# ESP_SENSOR_STATION_REV1.net
KiCad netlist of a schematic drawn in Altium Designer
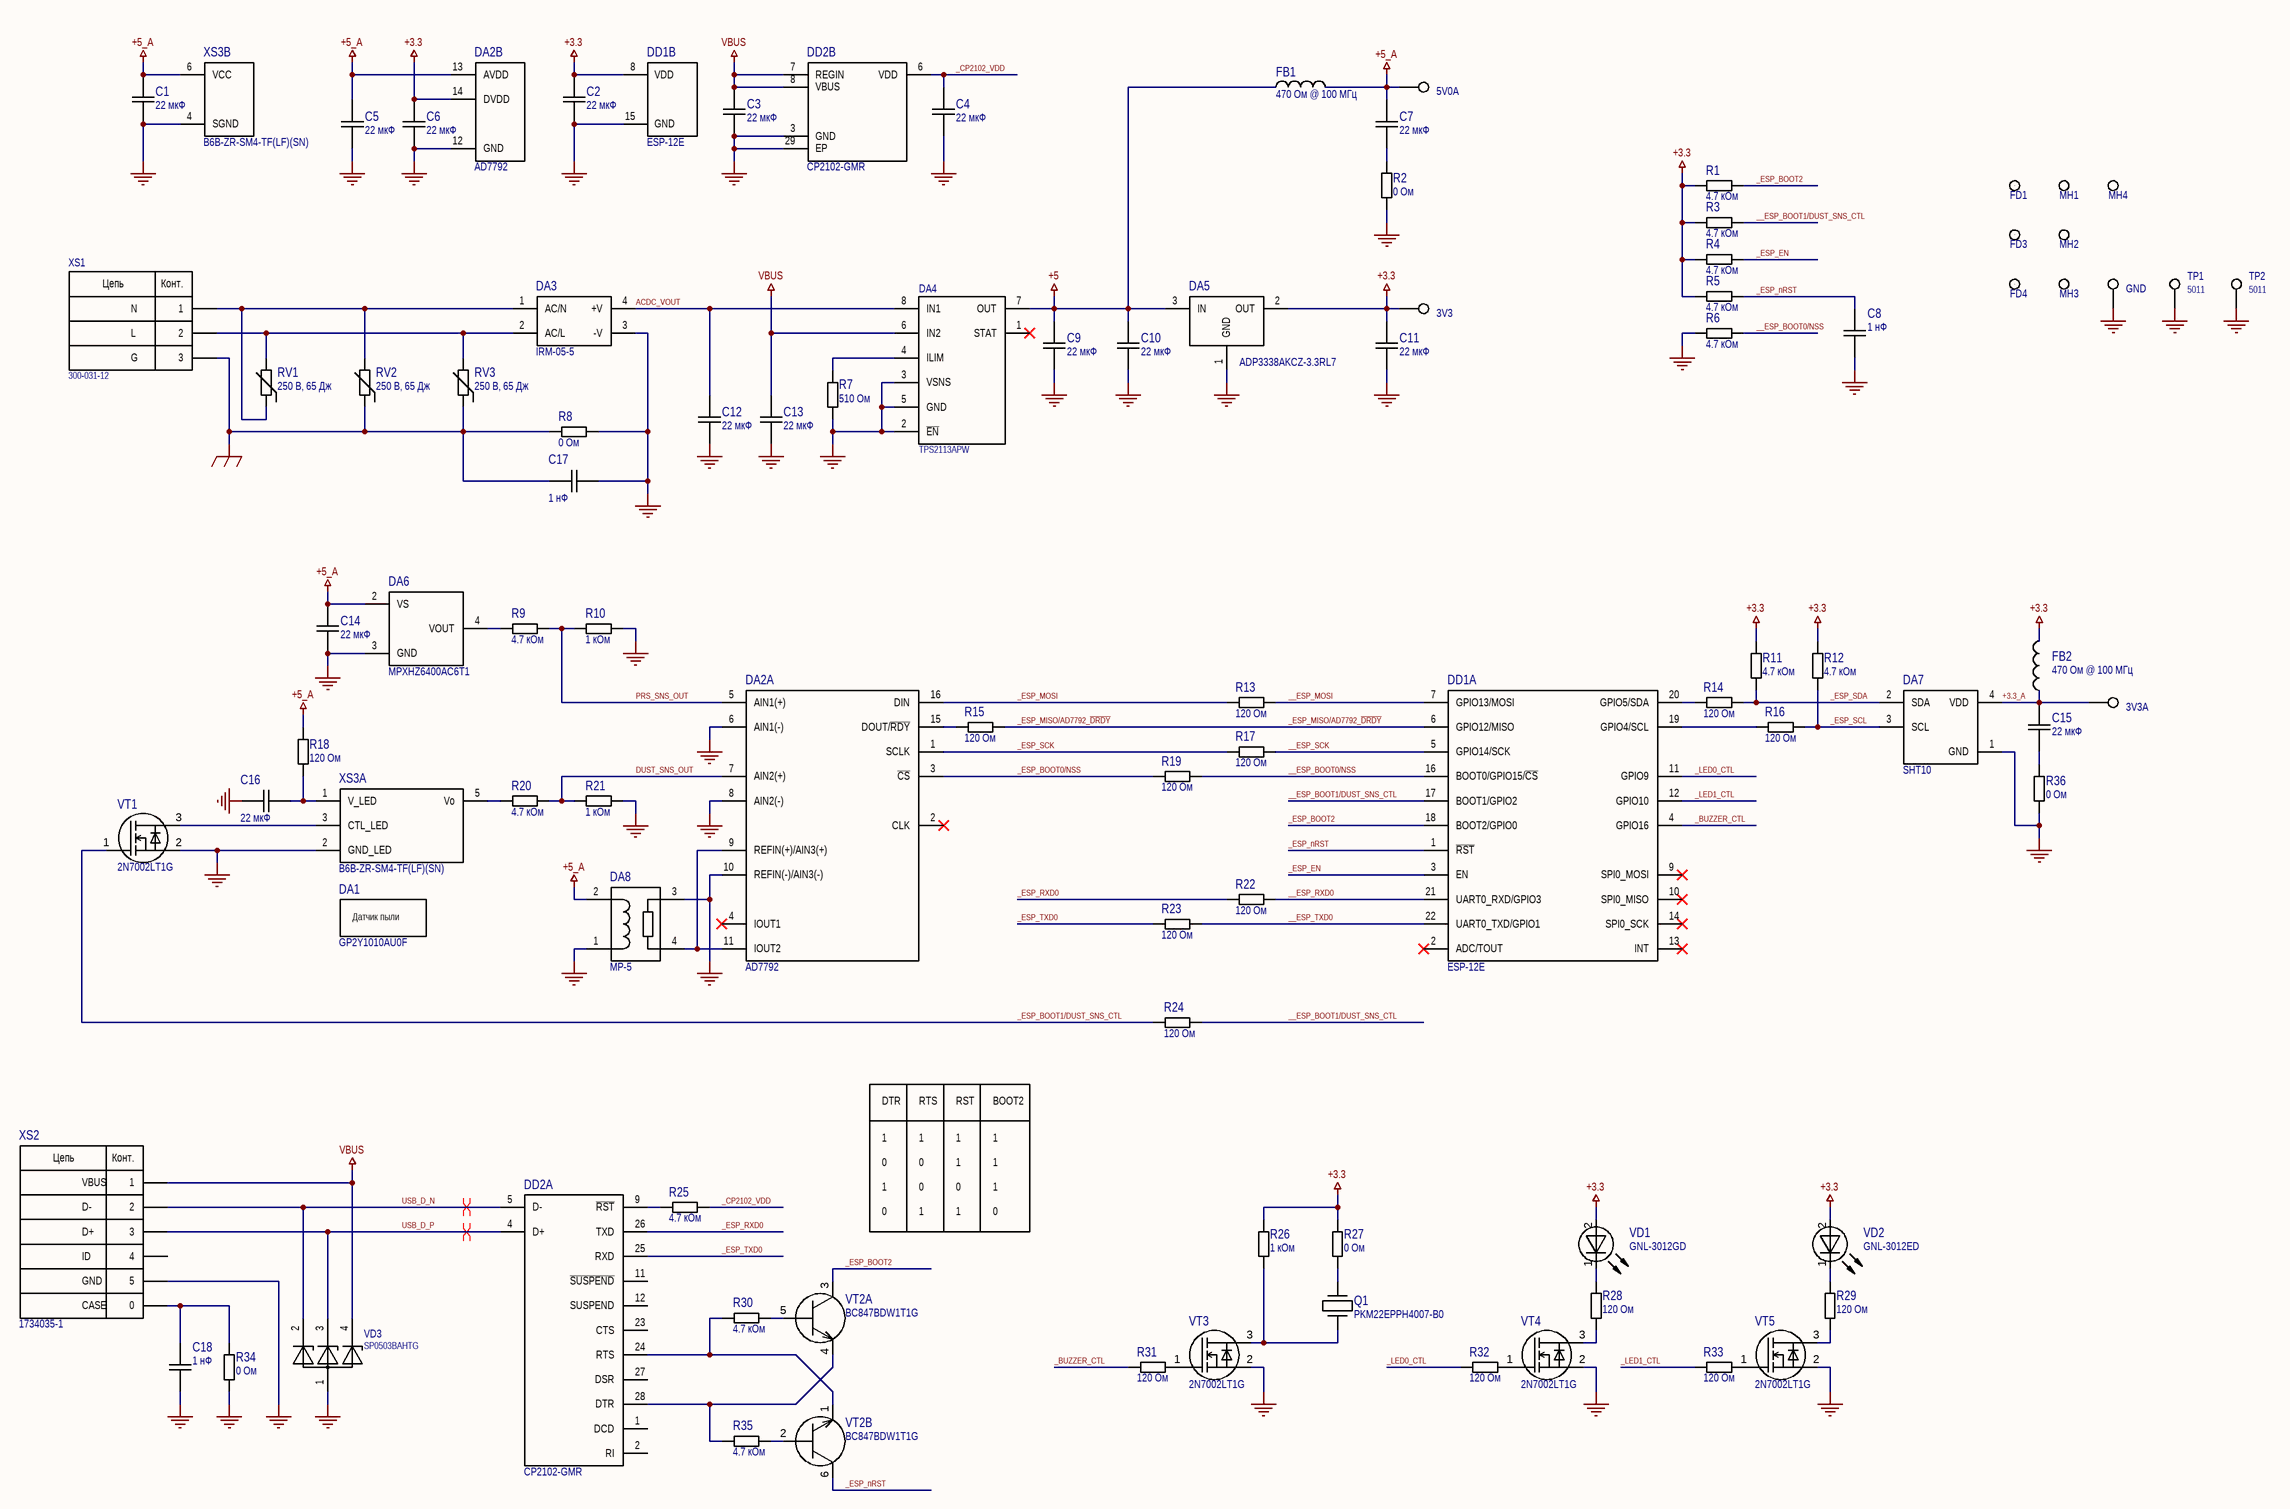
[diagram p0: ESP_SENSOR_STATION_REV1.SchDoc]

(export (version "E")
  (design (tool "Eeschema 10.0.6"))
  (components
    (comp (ref "3V3")
      (value "_TESTPOINT")
      (footprint "_TESTPOINT")
      (libsource (lib "ESP_SENSOR_STATION_REV1") (part "_TESTPOINT"))
    )
    (comp (ref "3V3A")
      (value "_TESTPOINT")
      (footprint "_TESTPOINT")
      (libsource (lib "ESP_SENSOR_STATION_REV1") (part "_TESTPOINT"))
    )
    (comp (ref "5V0A")
      (value "_TESTPOINT")
      (footprint "_TESTPOINT")
      (libsource (lib "ESP_SENSOR_STATION_REV1") (part "_TESTPOINT"))
    )
    (comp (ref "C1")
      (value "22 мкФ")
      (footprint "CAPC1608X08N")
      (libsource (lib "ESP_SENSOR_STATION_REV1") (part "GRM188R61A226ME15D"))
    )
    (comp (ref "C2")
      (value "22 мкФ")
      (footprint "CAPC1608X08N")
      (libsource (lib "ESP_SENSOR_STATION_REV1") (part "GRM188R61A226ME15D"))
    )
    (comp (ref "C3")
      (value "22 мкФ")
      (footprint "CAPC1608X08N")
      (libsource (lib "ESP_SENSOR_STATION_REV1") (part "GRM188R61A226ME15D"))
    )
    (comp (ref "C4")
      (value "22 мкФ")
      (footprint "CAPC1608X08N")
      (libsource (lib "ESP_SENSOR_STATION_REV1") (part "GRM188R61A226ME15D"))
    )
    (comp (ref "C5")
      (value "22 мкФ")
      (footprint "CAPC1608X08N")
      (libsource (lib "ESP_SENSOR_STATION_REV1") (part "GRM188R61A226ME15D"))
    )
    (comp (ref "C6")
      (value "22 мкФ")
      (footprint "CAPC1608X08N")
      (libsource (lib "ESP_SENSOR_STATION_REV1") (part "GRM188R61A226ME15D"))
    )
    (comp (ref "C7")
      (value "22 мкФ")
      (footprint "CAPC1608X08N")
      (libsource (lib "ESP_SENSOR_STATION_REV1") (part "GRM188R61A226ME15D"))
    )
    (comp (ref "C8")
      (value "1 нФ")
      (footprint "CAPC1608X08N")
      (libsource (lib "ESP_SENSOR_STATION_REV1") (part "GRM1885C2A102JA01D"))
    )
    (comp (ref "C9")
      (value "22 мкФ")
      (footprint "CAPC1608X08N")
      (libsource (lib "ESP_SENSOR_STATION_REV1") (part "GRM188R61A226ME15D"))
    )
    (comp (ref "C10")
      (value "22 мкФ")
      (footprint "CAPC1608X08N")
      (libsource (lib "ESP_SENSOR_STATION_REV1") (part "GRM188R61A226ME15D"))
    )
    (comp (ref "C11")
      (value "22 мкФ")
      (footprint "CAPC1608X08N")
      (libsource (lib "ESP_SENSOR_STATION_REV1") (part "GRM188R61A226ME15D"))
    )
    (comp (ref "C12")
      (value "22 мкФ")
      (footprint "CAPC1608X08N")
      (libsource (lib "ESP_SENSOR_STATION_REV1") (part "GRM188R61A226ME15D"))
    )
    (comp (ref "C13")
      (value "22 мкФ")
      (footprint "CAPC1608X08N")
      (libsource (lib "ESP_SENSOR_STATION_REV1") (part "GRM188R61A226ME15D"))
    )
    (comp (ref "C14")
      (value "22 мкФ")
      (footprint "CAPC1608X08N")
      (libsource (lib "ESP_SENSOR_STATION_REV1") (part "GRM188R61A226ME15D"))
    )
    (comp (ref "C15")
      (value "22 мкФ")
      (footprint "CAPC1608X08N")
      (libsource (lib "ESP_SENSOR_STATION_REV1") (part "GRM188R61A226ME15D"))
    )
    (comp (ref "C16")
      (value "22 мкФ")
      (footprint "CAPC1608X08N")
      (libsource (lib "ESP_SENSOR_STATION_REV1") (part "GRM188R61A226ME15D"))
    )
    (comp (ref "C17")
      (value "1 нФ")
      (footprint "CAPC1608X08N")
      (libsource (lib "ESP_SENSOR_STATION_REV1") (part "GRM1885C2A102JA01D"))
    )
    (comp (ref "C18")
      (value "1 нФ")
      (footprint "CAPC1608X08N")
      (libsource (lib "ESP_SENSOR_STATION_REV1") (part "GRM1885C2A102JA01D"))
    )
    (comp (ref "DA1")
      (value "GP2Y1010AU0F")
      (footprint "GP2Y1010AU0F")
      (libsource (lib "ESP_SENSOR_STATION_REV1") (part "GP2Y1010AU0F"))
    )
    (comp (ref "DA2")
      (value "AD7792")
      (footprint "TSOP65P640X120-16N")
      (libsource (lib "ESP_SENSOR_STATION_REV1") (part "AD7792"))
    )
    (comp (ref "DA3")
      (value "IRM-05-5")
      (footprint "IRM-05")
      (libsource (lib "ESP_SENSOR_STATION_REV1") (part "IRM-05-5"))
    )
    (comp (ref "DA4")
      (value "TPS2113APW")
      (footprint "TSOP65P640X120-8N")
      (libsource (lib "ESP_SENSOR_STATION_REV1") (part "TPS2113APW"))
    )
    (comp (ref "DA5")
      (value "ADP3338AKCZ-3.3RL7")
      (footprint "SOT230P700X180-4N")
      (libsource (lib "ESP_SENSOR_STATION_REV1") (part "ADP3338AKCZ-3.3RL7"))
    )
    (comp (ref "DA6")
      (value "MPXHZ6400AC6T1")
      (footprint "MPXHZ6400AC6T1")
      (libsource (lib "ESP_SENSOR_STATION_REV1") (part "MPXHZ6400AC6T1"))
    )
    (comp (ref "DA7")
      (value "SHT10")
      (footprint "SHT1x")
      (libsource (lib "ESP_SENSOR_STATION_REV1") (part "SHT10"))
    )
    (comp (ref "DA8")
      (value "MP-5")
      (footprint "MP-5")
      (libsource (lib "ESP_SENSOR_STATION_REV1") (part "MP-5"))
    )
    (comp (ref "DD1")
      (value "ESP-12E")
      (footprint "ESP-12E")
      (libsource (lib "ESP_SENSOR_STATION_REV1") (part "ESP-12E"))
    )
    (comp (ref "DD2")
      (value "CP2102-GMR")
      (footprint "QFN50P500X500X100_HS-29N")
      (libsource (lib "ESP_SENSOR_STATION_REV1") (part "CP2102-GMR"))
    )
    (comp (ref "FB1")
      (value "470 Ом @ 100 МГц")
      (footprint "INDC1608X08N")
      (libsource (lib "ESP_SENSOR_STATION_REV1") (part "BLM18PG471SN1D"))
    )
    (comp (ref "FB2")
      (value "470 Ом @ 100 МГц")
      (footprint "INDC1608X08N")
      (libsource (lib "ESP_SENSOR_STATION_REV1") (part "BLM18PG471SN1D"))
    )
    (comp (ref "FD1")
      (value "_FIDUCIAL")
      (footprint "_FIDUCIAL")
      (libsource (lib "ESP_SENSOR_STATION_REV1") (part "_FIDUCIAL"))
    )
    (comp (ref "FD3")
      (value "_FIDUCIAL")
      (footprint "_FIDUCIAL")
      (libsource (lib "ESP_SENSOR_STATION_REV1") (part "_FIDUCIAL"))
    )
    (comp (ref "FD4")
      (value "_FIDUCIAL")
      (footprint "_FIDUCIAL")
      (libsource (lib "ESP_SENSOR_STATION_REV1") (part "_FIDUCIAL"))
    )
    (comp (ref "GND")
      (value "_TESTPOINT")
      (footprint "_TESTPOINT")
      (libsource (lib "ESP_SENSOR_STATION_REV1") (part "_TESTPOINT"))
    )
    (comp (ref "MH1")
      (value "_MOUNTING_HOLE_M3")
      (footprint "_MOUNTING_HOLE_M3")
      (libsource (lib "ESP_SENSOR_STATION_REV1") (part "_MOUNTING_HOLE_M3"))
    )
    (comp (ref "MH2")
      (value "_MOUNTING_HOLE_M3")
      (footprint "_MOUNTING_HOLE_M3")
      (libsource (lib "ESP_SENSOR_STATION_REV1") (part "_MOUNTING_HOLE_M3"))
    )
    (comp (ref "MH3")
      (value "_MOUNTING_HOLE_M3")
      (footprint "_MOUNTING_HOLE_M3")
      (libsource (lib "ESP_SENSOR_STATION_REV1") (part "_MOUNTING_HOLE_M3"))
    )
    (comp (ref "MH4")
      (value "_MOUNTING_HOLE_M3")
      (footprint "_MOUNTING_HOLE_M3")
      (libsource (lib "ESP_SENSOR_STATION_REV1") (part "_MOUNTING_HOLE_M3"))
    )
    (comp (ref "Q1")
      (value "PKM22EPPH4007-B0")
      (footprint "PKM22EPPH4007-B0")
      (libsource (lib "ESP_SENSOR_STATION_REV1") (part "PKM22EPPH4007-B0"))
    )
    (comp (ref "R1")
      (value "4.7 кОм")
      (footprint "RESC1608X06N")
      (libsource (lib "ESP_SENSOR_STATION_REV1") (part "RC0603FR-074K7L"))
    )
    (comp (ref "R2")
      (value "0 Ом")
      (footprint "RESC1608X06N")
      (libsource (lib "ESP_SENSOR_STATION_REV1") (part "RC0603FR-070RL"))
    )
    (comp (ref "R3")
      (value "4.7 кОм")
      (footprint "RESC1608X06N")
      (libsource (lib "ESP_SENSOR_STATION_REV1") (part "RC0603FR-074K7L"))
    )
    (comp (ref "R4")
      (value "4.7 кОм")
      (footprint "RESC1608X06N")
      (libsource (lib "ESP_SENSOR_STATION_REV1") (part "RC0603FR-074K7L"))
    )
    (comp (ref "R5")
      (value "4.7 кОм")
      (footprint "RESC1608X06N")
      (libsource (lib "ESP_SENSOR_STATION_REV1") (part "RC0603FR-074K7L"))
    )
    (comp (ref "R6")
      (value "4.7 кОм")
      (footprint "RESC1608X06N")
      (libsource (lib "ESP_SENSOR_STATION_REV1") (part "RC0603FR-074K7L"))
    )
    (comp (ref "R7")
      (value "510 Ом")
      (footprint "RESC1608X06N")
      (libsource (lib "ESP_SENSOR_STATION_REV1") (part "RC0603FR-07510RL"))
    )
    (comp (ref "R8")
      (value "0 Ом")
      (footprint "RESC1608X06N")
      (libsource (lib "ESP_SENSOR_STATION_REV1") (part "RC0603FR-070RL"))
    )
    (comp (ref "R9")
      (value "4.7 кОм")
      (footprint "RESC1608X06N")
      (libsource (lib "ESP_SENSOR_STATION_REV1") (part "RC0603FR-074K7L"))
    )
    (comp (ref "R10")
      (value "1 кОм")
      (footprint "RESC1608X06N")
      (libsource (lib "ESP_SENSOR_STATION_REV1") (part "RC0603FR-071KL"))
    )
    (comp (ref "R11")
      (value "4.7 кОм")
      (footprint "RESC1608X06N")
      (libsource (lib "ESP_SENSOR_STATION_REV1") (part "RC0603FR-074K7L"))
    )
    (comp (ref "R12")
      (value "4.7 кОм")
      (footprint "RESC1608X06N")
      (libsource (lib "ESP_SENSOR_STATION_REV1") (part "RC0603FR-074K7L"))
    )
    (comp (ref "R13")
      (value "120 Ом")
      (footprint "RESC1608X06N")
      (libsource (lib "ESP_SENSOR_STATION_REV1") (part "RC0603FR-07120RL"))
    )
    (comp (ref "R14")
      (value "120 Ом")
      (footprint "RESC1608X06N")
      (libsource (lib "ESP_SENSOR_STATION_REV1") (part "RC0603FR-07120RL"))
    )
    (comp (ref "R15")
      (value "120 Ом")
      (footprint "RESC1608X06N")
      (libsource (lib "ESP_SENSOR_STATION_REV1") (part "RC0603FR-07120RL"))
    )
    (comp (ref "R16")
      (value "120 Ом")
      (footprint "RESC1608X06N")
      (libsource (lib "ESP_SENSOR_STATION_REV1") (part "RC0603FR-07120RL"))
    )
    (comp (ref "R17")
      (value "120 Ом")
      (footprint "RESC1608X06N")
      (libsource (lib "ESP_SENSOR_STATION_REV1") (part "RC0603FR-07120RL"))
    )
    (comp (ref "R18")
      (value "120 Ом")
      (footprint "RESC1608X06N")
      (libsource (lib "ESP_SENSOR_STATION_REV1") (part "RC0603FR-07120RL"))
    )
    (comp (ref "R19")
      (value "120 Ом")
      (footprint "RESC1608X06N")
      (libsource (lib "ESP_SENSOR_STATION_REV1") (part "RC0603FR-07120RL"))
    )
    (comp (ref "R20")
      (value "4.7 кОм")
      (footprint "RESC1608X06N")
      (libsource (lib "ESP_SENSOR_STATION_REV1") (part "RC0603FR-074K7L"))
    )
    (comp (ref "R21")
      (value "1 кОм")
      (footprint "RESC1608X06N")
      (libsource (lib "ESP_SENSOR_STATION_REV1") (part "RC0603FR-071KL"))
    )
    (comp (ref "R22")
      (value "120 Ом")
      (footprint "RESC1608X06N")
      (libsource (lib "ESP_SENSOR_STATION_REV1") (part "RC0603FR-07120RL"))
    )
    (comp (ref "R23")
      (value "120 Ом")
      (footprint "RESC1608X06N")
      (libsource (lib "ESP_SENSOR_STATION_REV1") (part "RC0603FR-07120RL"))
    )
    (comp (ref "R24")
      (value "120 Ом")
      (footprint "RESC1608X06N")
      (libsource (lib "ESP_SENSOR_STATION_REV1") (part "RC0603FR-07120RL"))
    )
    (comp (ref "R25")
      (value "4.7 кОм")
      (footprint "RESC1608X06N")
      (libsource (lib "ESP_SENSOR_STATION_REV1") (part "RC0603FR-074K7L"))
    )
    (comp (ref "R26")
      (value "1 кОм")
      (footprint "RESC1608X06N")
      (libsource (lib "ESP_SENSOR_STATION_REV1") (part "RC0603FR-071KL"))
    )
    (comp (ref "R27")
      (value "0 Ом")
      (footprint "RESC1608X06N")
      (libsource (lib "ESP_SENSOR_STATION_REV1") (part "RC0603FR-070RL"))
    )
    (comp (ref "R28")
      (value "120 Ом")
      (footprint "RESC1608X06N")
      (libsource (lib "ESP_SENSOR_STATION_REV1") (part "RC0603FR-07120RL"))
    )
    (comp (ref "R29")
      (value "120 Ом")
      (footprint "RESC1608X06N")
      (libsource (lib "ESP_SENSOR_STATION_REV1") (part "RC0603FR-07120RL"))
    )
    (comp (ref "R30")
      (value "4.7 кОм")
      (footprint "RESC1608X06N")
      (libsource (lib "ESP_SENSOR_STATION_REV1") (part "RC0603FR-074K7L"))
    )
    (comp (ref "R31")
      (value "120 Ом")
      (footprint "RESC1608X06N")
      (libsource (lib "ESP_SENSOR_STATION_REV1") (part "RC0603FR-07120RL"))
    )
    (comp (ref "R32")
      (value "120 Ом")
      (footprint "RESC1608X06N")
      (libsource (lib "ESP_SENSOR_STATION_REV1") (part "RC0603FR-07120RL"))
    )
    (comp (ref "R33")
      (value "120 Ом")
      (footprint "RESC1608X06N")
      (libsource (lib "ESP_SENSOR_STATION_REV1") (part "RC0603FR-07120RL"))
    )
    (comp (ref "R34")
      (value "0 Ом")
      (footprint "RESC1608X06N")
      (libsource (lib "ESP_SENSOR_STATION_REV1") (part "RC0603FR-070RL"))
    )
    (comp (ref "R35")
      (value "4.7 кОм")
      (footprint "RESC1608X06N")
      (libsource (lib "ESP_SENSOR_STATION_REV1") (part "RC0603FR-074K7L"))
    )
    (comp (ref "R36")
      (value "0 Ом")
      (footprint "RESC1608X06N")
      (libsource (lib "ESP_SENSOR_STATION_REV1") (part "RC0603FR-070RL"))
    )
    (comp (ref "RV1")
      (value "250 В, 65 Дж")
      (footprint "B72214S0251K101")
      (libsource (lib "ESP_SENSOR_STATION_REV1") (part "B72214S0251K101"))
    )
    (comp (ref "RV2")
      (value "250 В, 65 Дж")
      (footprint "B72214S0251K101")
      (libsource (lib "ESP_SENSOR_STATION_REV1") (part "B72214S0251K101"))
    )
    (comp (ref "RV3")
      (value "250 В, 65 Дж")
      (footprint "B72214S0251K101")
      (libsource (lib "ESP_SENSOR_STATION_REV1") (part "B72214S0251K101"))
    )
    (comp (ref "TP1")
      (value "5011")
      (footprint "5011")
      (libsource (lib "ESP_SENSOR_STATION_REV1") (part "5011"))
    )
    (comp (ref "TP2")
      (value "5011")
      (footprint "5011")
      (libsource (lib "ESP_SENSOR_STATION_REV1") (part "5011"))
    )
    (comp (ref "VD1")
      (value "GNL-3012GD")
      (footprint "GNL-3012GD")
      (libsource (lib "ESP_SENSOR_STATION_REV1") (part "GNL-3012GD"))
    )
    (comp (ref "VD2")
      (value "GNL-3012ED")
      (footprint "GNL-3012ED")
      (libsource (lib "ESP_SENSOR_STATION_REV1") (part "GNL-3012ED"))
    )
    (comp (ref "VD3")
      (value "SP0503BAHTG")
      (footprint "SOT190P237X122-4N")
      (libsource (lib "ESP_SENSOR_STATION_REV1") (part "SP0503BAHTG"))
    )
    (comp (ref "VT1")
      (value "2N7002LT1G")
      (footprint "SOT95P237X111-3N")
      (libsource (lib "ESP_SENSOR_STATION_REV1") (part "2N7002LT1G"))
    )
    (comp (ref "VT2")
      (value "BC847BDW1T1G")
      (footprint "SOT65P210X110-6N")
      (libsource (lib "ESP_SENSOR_STATION_REV1") (part "BC847BDW1T1G"))
    )
    (comp (ref "VT3")
      (value "2N7002LT1G")
      (footprint "SOT95P237X111-3N")
      (libsource (lib "ESP_SENSOR_STATION_REV1") (part "2N7002LT1G"))
    )
    (comp (ref "VT4")
      (value "2N7002LT1G")
      (footprint "SOT95P237X111-3N")
      (libsource (lib "ESP_SENSOR_STATION_REV1") (part "2N7002LT1G"))
    )
    (comp (ref "VT5")
      (value "2N7002LT1G")
      (footprint "SOT95P237X111-3N")
      (libsource (lib "ESP_SENSOR_STATION_REV1") (part "2N7002LT1G"))
    )
    (comp (ref "XS1")
      (value "300-031-12")
      (footprint "300-031-12")
      (libsource (lib "ESP_SENSOR_STATION_REV1") (part "300-031-12"))
    )
    (comp (ref "XS2")
      (value "1734035-1")
      (footprint "1734035-1")
      (libsource (lib "ESP_SENSOR_STATION_REV1") (part "1734035-1"))
    )
    (comp (ref "XS3")
      (value "B6B-ZR-SM4-TF(LF)(SN)")
      (footprint "B6B-ZR-SM4-TF(LF)(SN)")
      (libsource (lib "ESP_SENSOR_STATION_REV1") (part "B6B-ZR-SM4-TF(LF)(SN)"))
    )
  )
  (nets
    (net (code "1") (name "+3.3") (class "Default")
      (node (ref "3V3") (pin "1") (pinfunction "1_1") (pintype "passive"))
      (node (ref "C11") (pin "2") (pinfunction "2_2") (pintype "passive"))
      (node (ref "C2") (pin "2") (pinfunction "2_2") (pintype "passive"))
      (node (ref "C6") (pin "2") (pinfunction "2_2") (pintype "passive"))
      (node (ref "DA2") (pin "14") (pinfunction "DVDD_14") (pintype "passive"))
      (node (ref "DA5") (pin "2") (pinfunction "OUT_2") (pintype "passive"))
      (node (ref "DD1") (pin "8") (pinfunction "VDD_8") (pintype "passive"))
      (node (ref "FB2") (pin "2") (pinfunction "2_2") (pintype "passive"))
      (node (ref "R1") (pin "1") (pinfunction "1_1") (pintype "passive"))
      (node (ref "R11") (pin "1") (pinfunction "1_1") (pintype "passive"))
      (node (ref "R12") (pin "1") (pinfunction "1_1") (pintype "passive"))
      (node (ref "R26") (pin "2") (pinfunction "2_2") (pintype "passive"))
      (node (ref "R27") (pin "2") (pinfunction "2_2") (pintype "passive"))
      (node (ref "R3") (pin "1") (pinfunction "1_1") (pintype "passive"))
      (node (ref "R4") (pin "1") (pinfunction "1_1") (pintype "passive"))
      (node (ref "R5") (pin "1") (pinfunction "1_1") (pintype "passive"))
      (node (ref "VD1") (pin "2") (pinfunction "A_2") (pintype "passive"))
      (node (ref "VD2") (pin "2") (pinfunction "A_2") (pintype "passive"))
    )
    (net (code "2") (name "+5") (class "Default")
      (node (ref "C10") (pin "2") (pinfunction "2_2") (pintype "passive"))
      (node (ref "C9") (pin "2") (pinfunction "2_2") (pintype "passive"))
      (node (ref "DA4") (pin "7") (pinfunction "OUT_7") (pintype "passive"))
      (node (ref "DA5") (pin "3") (pinfunction "IN_3") (pintype "passive"))
      (node (ref "FB1") (pin "1") (pinfunction "1_1") (pintype "passive"))
    )
    (net (code "3") (name "+5_A") (class "Default")
      (node (ref "5V0A") (pin "1") (pinfunction "1_1") (pintype "passive"))
      (node (ref "C1") (pin "2") (pinfunction "2_2") (pintype "passive"))
      (node (ref "C14") (pin "2") (pinfunction "2_2") (pintype "passive"))
      (node (ref "C5") (pin "2") (pinfunction "2_2") (pintype "passive"))
      (node (ref "C7") (pin "2") (pinfunction "2_2") (pintype "passive"))
      (node (ref "DA2") (pin "13") (pinfunction "AVDD_13") (pintype "passive"))
      (node (ref "DA6") (pin "2") (pinfunction "VS_2") (pintype "passive"))
      (node (ref "DA8") (pin "2") (pinfunction "2_2") (pintype "passive"))
      (node (ref "FB1") (pin "2") (pinfunction "2_2") (pintype "passive"))
      (node (ref "R18") (pin "1") (pinfunction "1_1") (pintype "passive"))
      (node (ref "XS3") (pin "6") (pinfunction "VCC_6") (pintype "passive"))
    )
    (net (code "4") (name "/+3.3_A") (class "Default")
      (node (ref "3V3A") (pin "1") (pinfunction "1_1") (pintype "passive"))
      (node (ref "C15") (pin "2") (pinfunction "2_2") (pintype "passive"))
      (node (ref "DA7") (pin "4") (pinfunction "VDD_4") (pintype "passive"))
      (node (ref "FB2") (pin "1") (pinfunction "1_1") (pintype "passive"))
    )
    (net (code "5") (name "/ACDC_VOUT") (class "Default")
      (node (ref "C12") (pin "2") (pinfunction "2_2") (pintype "passive"))
      (node (ref "DA3") (pin "4") (pinfunction "+V_4") (pintype "passive"))
      (node (ref "DA4") (pin "8") (pinfunction "IN1_8") (pintype "passive"))
    )
    (net (code "6") (name "/DUST_SNS_OUT") (class "Default")
      (node (ref "DA2") (pin "7") (pinfunction "AIN2(+)_7") (pintype "passive"))
      (node (ref "R20") (pin "2") (pinfunction "2_2") (pintype "passive"))
      (node (ref "R21") (pin "2") (pinfunction "2_2") (pintype "passive"))
    )
    (net (code "7") (name "/PRS_SNS_OUT") (class "Default")
      (node (ref "DA2") (pin "5") (pinfunction "AIN1(+)_5") (pintype "passive"))
      (node (ref "R10") (pin "2") (pinfunction "2_2") (pintype "passive"))
      (node (ref "R9") (pin "2") (pinfunction "2_2") (pintype "passive"))
    )
    (net (code "8") (name "/USB_D_N") (class "Default")
      (node (ref "DD2") (pin "5") (pinfunction "D-_5") (pintype "passive"))
      (node (ref "VD3") (pin "2") (pinfunction "2_2") (pintype "passive"))
      (node (ref "XS2") (pin "2") (pinfunction "2_2") (pintype "passive"))
    )
    (net (code "9") (name "/USB_D_P") (class "Default")
      (node (ref "DD2") (pin "4") (pinfunction "D+_4") (pintype "passive"))
      (node (ref "VD3") (pin "3") (pinfunction "3_3") (pintype "passive"))
      (node (ref "XS2") (pin "3") (pinfunction "3_3") (pintype "passive"))
    )
    (net (code "10") (name "/_BUZZER_CTL") (class "Default")
      (node (ref "DD1") (pin "4") (pinfunction "GPIO16_4") (pintype "passive"))
      (node (ref "R31") (pin "2") (pinfunction "2_2") (pintype "passive"))
    )
    (net (code "11") (name "/_CP2102_VDD") (class "Default")
      (node (ref "C4") (pin "2") (pinfunction "2_2") (pintype "passive"))
      (node (ref "DD2") (pin "6") (pinfunction "VDD_6") (pintype "passive"))
      (node (ref "R25") (pin "1") (pinfunction "1_1") (pintype "passive"))
    )
    (net (code "12") (name "/_ESP_BOOT0{slash}NSS") (class "Default")
      (node (ref "DA2") (pin "3") (pinfunction "~{CS}_3") (pintype "passive"))
      (node (ref "R19") (pin "2") (pinfunction "2_2") (pintype "passive"))
    )
    (net (code "13") (name "/_ESP_BOOT1{slash}DUST_SNS_CTL") (class "Default")
      (node (ref "R24") (pin "2") (pinfunction "2_2") (pintype "passive"))
      (node (ref "VT1") (pin "1") (pinfunction "G_1") (pintype "passive"))
    )
    (net (code "14") (name "/_ESP_BOOT2") (class "Default")
      (node (ref "DD1") (pin "18") (pinfunction "BOOT2/GPIO0_18") (pintype "passive"))
      (node (ref "R1") (pin "2") (pinfunction "2_2") (pintype "passive"))
      (node (ref "VT2") (pin "3") (pinfunction "C1_3") (pintype "passive"))
    )
    (net (code "15") (name "/_ESP_EN") (class "Default")
      (node (ref "DD1") (pin "3") (pinfunction "EN_3") (pintype "passive"))
      (node (ref "R4") (pin "2") (pinfunction "2_2") (pintype "passive"))
    )
    (net (code "16") (name "/_ESP_MISO{slash}AD7792_~{DRDY}") (class "Default")
      (node (ref "DD1") (pin "6") (pinfunction "GPIO12/MISO_6") (pintype "passive"))
      (node (ref "R15") (pin "1") (pinfunction "1_1") (pintype "passive"))
    )
    (net (code "17") (name "/_ESP_MOSI") (class "Default")
      (node (ref "DA2") (pin "16") (pinfunction "DIN_16") (pintype "passive"))
      (node (ref "R13") (pin "2") (pinfunction "2_2") (pintype "passive"))
    )
    (net (code "18") (name "/_ESP_RXD0") (class "Default")
      (node (ref "DD2") (pin "26") (pinfunction "TXD_26") (pintype "passive"))
      (node (ref "R22") (pin "2") (pinfunction "2_2") (pintype "passive"))
    )
    (net (code "19") (name "/_ESP_SCK") (class "Default")
      (node (ref "DA2") (pin "1") (pinfunction "SCLK_1") (pintype "passive"))
      (node (ref "R17") (pin "2") (pinfunction "2_2") (pintype "passive"))
    )
    (net (code "20") (name "/_ESP_SCL") (class "Default")
      (node (ref "DA7") (pin "3") (pinfunction "SCL_3") (pintype "passive"))
      (node (ref "R12") (pin "2") (pinfunction "2_2") (pintype "passive"))
      (node (ref "R16") (pin "1") (pinfunction "1_1") (pintype "passive"))
    )
    (net (code "21") (name "/_ESP_SDA") (class "Default")
      (node (ref "DA7") (pin "2") (pinfunction "SDA_2") (pintype "passive"))
      (node (ref "R11") (pin "2") (pinfunction "2_2") (pintype "passive"))
      (node (ref "R14") (pin "1") (pinfunction "1_1") (pintype "passive"))
    )
    (net (code "22") (name "/_ESP_TXD0") (class "Default")
      (node (ref "DD2") (pin "25") (pinfunction "RXD_25") (pintype "passive"))
      (node (ref "R23") (pin "2") (pinfunction "2_2") (pintype "passive"))
    )
    (net (code "23") (name "/_ESP_nRST") (class "Default")
      (node (ref "C8") (pin "2") (pinfunction "2_2") (pintype "passive"))
      (node (ref "DD1") (pin "1") (pinfunction "~{RST}_1") (pintype "passive"))
      (node (ref "R5") (pin "2") (pinfunction "2_2") (pintype "passive"))
      (node (ref "VT2") (pin "6") (pinfunction "C2_6") (pintype "passive"))
    )
    (net (code "24") (name "/_LED0_CTL") (class "Default")
      (node (ref "DD1") (pin "11") (pinfunction "GPIO9_11") (pintype "passive"))
      (node (ref "R32") (pin "2") (pinfunction "2_2") (pintype "passive"))
    )
    (net (code "25") (name "/_LED1_CTL") (class "Default")
      (node (ref "DD1") (pin "12") (pinfunction "GPIO10_12") (pintype "passive"))
      (node (ref "R33") (pin "2") (pinfunction "2_2") (pintype "passive"))
    )
    (net (code "26") (name "/__ESP_BOOT0{slash}NSS") (class "Default")
      (node (ref "DD1") (pin "16") (pinfunction "BOOT0/GPIO15/~{CS}_16") (pintype "passive"))
      (node (ref "R19") (pin "1") (pinfunction "1_1") (pintype "passive"))
      (node (ref "R6") (pin "2") (pinfunction "2_2") (pintype "passive"))
    )
    (net (code "27") (name "/__ESP_BOOT1{slash}DUST_SNS_CTL") (class "Default")
      (node (ref "DD1") (pin "17") (pinfunction "BOOT1/GPIO2_17") (pintype "passive"))
      (node (ref "R24") (pin "1") (pinfunction "1_1") (pintype "passive"))
      (node (ref "R3") (pin "2") (pinfunction "2_2") (pintype "passive"))
    )
    (net (code "28") (name "/__ESP_MOSI") (class "Default")
      (node (ref "DD1") (pin "7") (pinfunction "GPIO13/MOSI_7") (pintype "passive"))
      (node (ref "R13") (pin "1") (pinfunction "1_1") (pintype "passive"))
    )
    (net (code "29") (name "/__ESP_RXD0") (class "Default")
      (node (ref "DD1") (pin "21") (pinfunction "UART0_RXD/GPIO3_21") (pintype "passive"))
      (node (ref "R22") (pin "1") (pinfunction "1_1") (pintype "passive"))
    )
    (net (code "30") (name "/__ESP_SCK") (class "Default")
      (node (ref "DD1") (pin "5") (pinfunction "GPIO14/SCK_5") (pintype "passive"))
      (node (ref "R17") (pin "1") (pinfunction "1_1") (pintype "passive"))
    )
    (net (code "31") (name "/__ESP_TXD0") (class "Default")
      (node (ref "DD1") (pin "22") (pinfunction "UART0_TXD/GPIO1_22") (pintype "passive"))
      (node (ref "R23") (pin "1") (pinfunction "1_1") (pintype "passive"))
    )
    (net (code "32") (name "GND") (class "Default")
      (node (ref "C1") (pin "1") (pinfunction "1_1") (pintype "passive"))
      (node (ref "C10") (pin "1") (pinfunction "1_1") (pintype "passive"))
      (node (ref "C11") (pin "1") (pinfunction "1_1") (pintype "passive"))
      (node (ref "C12") (pin "1") (pinfunction "1_1") (pintype "passive"))
      (node (ref "C13") (pin "1") (pinfunction "1_1") (pintype "passive"))
      (node (ref "C14") (pin "1") (pinfunction "1_1") (pintype "passive"))
      (node (ref "C16") (pin "1") (pinfunction "1_1") (pintype "passive"))
      (node (ref "C17") (pin "1") (pinfunction "1_1") (pintype "passive"))
      (node (ref "C18") (pin "2") (pinfunction "2_2") (pintype "passive"))
      (node (ref "C2") (pin "1") (pinfunction "1_1") (pintype "passive"))
      (node (ref "C3") (pin "1") (pinfunction "1_1") (pintype "passive"))
      (node (ref "C4") (pin "1") (pinfunction "1_1") (pintype "passive"))
      (node (ref "C5") (pin "1") (pinfunction "1_1") (pintype "passive"))
      (node (ref "C6") (pin "1") (pinfunction "1_1") (pintype "passive"))
      (node (ref "C8") (pin "1") (pinfunction "1_1") (pintype "passive"))
      (node (ref "C9") (pin "1") (pinfunction "1_1") (pintype "passive"))
      (node (ref "DA2") (pin "10") (pinfunction "REFIN(-)/AIN3(-)_10") (pintype "passive"))
      (node (ref "DA2") (pin "12") (pinfunction "GND_12") (pintype "passive"))
      (node (ref "DA2") (pin "6") (pinfunction "AIN1(-)_6") (pintype "passive"))
      (node (ref "DA2") (pin "8") (pinfunction "AIN2(-)_8") (pintype "passive"))
      (node (ref "DA3") (pin "3") (pinfunction "-V_3") (pintype "passive"))
      (node (ref "DA4") (pin "2") (pinfunction "~{EN}_2") (pintype "passive"))
      (node (ref "DA4") (pin "3") (pinfunction "VSNS_3") (pintype "passive"))
      (node (ref "DA4") (pin "5") (pinfunction "GND_5") (pintype "passive"))
      (node (ref "DA5") (pin "1") (pinfunction "GND_1") (pintype "passive"))
      (node (ref "DA6") (pin "3") (pinfunction "GND_3") (pintype "passive"))
      (node (ref "DA7") (pin "1") (pinfunction "GND_1") (pintype "passive"))
      (node (ref "DA8") (pin "1") (pinfunction "1_1") (pintype "passive"))
      (node (ref "DA8") (pin "3") (pinfunction "3_3") (pintype "passive"))
      (node (ref "DD1") (pin "15") (pinfunction "GND_15") (pintype "passive"))
      (node (ref "DD2") (pin "29") (pinfunction "EP_29") (pintype "passive"))
      (node (ref "DD2") (pin "3") (pinfunction "GND_3") (pintype "passive"))
      (node (ref "GND") (pin "1") (pinfunction "1_1") (pintype "passive"))
      (node (ref "R10") (pin "1") (pinfunction "1_1") (pintype "passive"))
      (node (ref "R2") (pin "2") (pinfunction "2_2") (pintype "passive"))
      (node (ref "R21") (pin "1") (pinfunction "1_1") (pintype "passive"))
      (node (ref "R34") (pin "1") (pinfunction "1_1") (pintype "passive"))
      (node (ref "R36") (pin "2") (pinfunction "2_2") (pintype "passive"))
      (node (ref "R6") (pin "1") (pinfunction "1_1") (pintype "passive"))
      (node (ref "R7") (pin "1") (pinfunction "1_1") (pintype "passive"))
      (node (ref "R8") (pin "1") (pinfunction "1_1") (pintype "passive"))
      (node (ref "TP1") (pin "1") (pinfunction "1_1") (pintype "passive"))
      (node (ref "TP2") (pin "1") (pinfunction "1_1") (pintype "passive"))
      (node (ref "VD3") (pin "1") (pinfunction "1_1") (pintype "passive"))
      (node (ref "VT1") (pin "2") (pinfunction "S_2") (pintype "passive"))
      (node (ref "VT3") (pin "2") (pinfunction "S_2") (pintype "passive"))
      (node (ref "VT4") (pin "2") (pinfunction "S_2") (pintype "passive"))
      (node (ref "VT5") (pin "2") (pinfunction "S_2") (pintype "passive"))
      (node (ref "XS2") (pin "5") (pinfunction "5_5") (pintype "passive"))
      (node (ref "XS3") (pin "2") (pinfunction "GND_LED_2") (pintype "passive"))
      (node (ref "XS3") (pin "4") (pinfunction "SGND_4") (pintype "passive"))
    )
    (net (code "33") (name "Net-(C7-Pad1)") (class "Default")
      (node (ref "C7") (pin "1") (pinfunction "1_1") (pintype "passive"))
      (node (ref "R2") (pin "1") (pinfunction "1_1") (pintype "passive"))
    )
    (net (code "34") (name "Net-(C15-Pad1)") (class "Default")
      (node (ref "C15") (pin "1") (pinfunction "1_1") (pintype "passive"))
      (node (ref "R36") (pin "1") (pinfunction "1_1") (pintype "passive"))
    )
    (net (code "35") (name "Net-(C18-Pad1)") (class "Default")
      (node (ref "C18") (pin "1") (pinfunction "1_1") (pintype "passive"))
      (node (ref "R34") (pin "2") (pinfunction "2_2") (pintype "passive"))
      (node (ref "XS2") (pin "0") (pinfunction "0_0") (pintype "passive"))
    )
    (net (code "36") (name "Net-(DA2A-DOUT{slash}~{RDY})") (class "Default")
      (node (ref "DA2") (pin "15") (pinfunction "DOUT/~{RDY}_15") (pintype "passive"))
      (node (ref "R15") (pin "2") (pinfunction "2_2") (pintype "passive"))
    )
    (net (code "37") (name "Net-(DA2A-IOUT2)") (class "Default")
      (node (ref "DA2") (pin "11") (pinfunction "IOUT2_11") (pintype "passive"))
      (node (ref "DA2") (pin "9") (pinfunction "REFIN(+)/AIN3(+)_9") (pintype "passive"))
      (node (ref "DA8") (pin "4") (pinfunction "4_4") (pintype "passive"))
    )
    (net (code "38") (name "Net-(DA3-AC{slash}L)") (class "Default")
      (node (ref "DA3") (pin "2") (pinfunction "AC/L_2") (pintype "passive"))
      (node (ref "RV1") (pin "2") (pinfunction "2_2") (pintype "passive"))
      (node (ref "RV3") (pin "2") (pinfunction "2_2") (pintype "passive"))
      (node (ref "XS1") (pin "2") (pinfunction "2_2") (pintype "passive"))
    )
    (net (code "39") (name "Net-(DA3-AC{slash}N)") (class "Default")
      (node (ref "DA3") (pin "1") (pinfunction "AC/N_1") (pintype "passive"))
      (node (ref "RV1") (pin "1") (pinfunction "1_1") (pintype "passive"))
      (node (ref "RV2") (pin "2") (pinfunction "2_2") (pintype "passive"))
      (node (ref "XS1") (pin "1") (pinfunction "1_1") (pintype "passive"))
    )
    (net (code "40") (name "Net-(DA4-ILIM)") (class "Default")
      (node (ref "DA4") (pin "4") (pinfunction "ILIM_4") (pintype "passive"))
      (node (ref "R7") (pin "2") (pinfunction "2_2") (pintype "passive"))
    )
    (net (code "41") (name "Net-(DA6-VOUT)") (class "Default")
      (node (ref "DA6") (pin "4") (pinfunction "VOUT_4") (pintype "passive"))
      (node (ref "R9") (pin "1") (pinfunction "1_1") (pintype "passive"))
    )
    (net (code "42") (name "Net-(DD1A-GPIO4{slash}SCL)") (class "Default")
      (node (ref "DD1") (pin "19") (pinfunction "GPIO4/SCL_19") (pintype "passive"))
      (node (ref "R16") (pin "2") (pinfunction "2_2") (pintype "passive"))
    )
    (net (code "43") (name "Net-(DD1A-GPIO5{slash}SDA)") (class "Default")
      (node (ref "DD1") (pin "20") (pinfunction "GPIO5/SDA_20") (pintype "passive"))
      (node (ref "R14") (pin "2") (pinfunction "2_2") (pintype "passive"))
    )
    (net (code "44") (name "Net-(DD2A-DTR)") (class "Default")
      (node (ref "DD2") (pin "28") (pinfunction "DTR_28") (pintype "passive"))
      (node (ref "R35") (pin "1") (pinfunction "1_1") (pintype "passive"))
      (node (ref "VT2") (pin "4") (pinfunction "E1_4") (pintype "passive"))
    )
    (net (code "45") (name "Net-(DD2A-RTS)") (class "Default")
      (node (ref "DD2") (pin "24") (pinfunction "RTS_24") (pintype "passive"))
      (node (ref "R30") (pin "1") (pinfunction "1_1") (pintype "passive"))
      (node (ref "VT2") (pin "1") (pinfunction "E2_1") (pintype "passive"))
    )
    (net (code "46") (name "Net-(DD2A-~{RST})") (class "Default")
      (node (ref "DD2") (pin "9") (pinfunction "~{RST}_9") (pintype "passive"))
      (node (ref "R25") (pin "2") (pinfunction "2_2") (pintype "passive"))
    )
    (net (code "47") (name "Net-(Q1-Pad2)") (class "Default")
      (node (ref "Q1") (pin "2") (pinfunction "2_2") (pintype "passive"))
      (node (ref "R27") (pin "1") (pinfunction "1_1") (pintype "passive"))
    )
    (net (code "48") (name "Net-(VD1-C)") (class "Default")
      (node (ref "R28") (pin "2") (pinfunction "2_2") (pintype "passive"))
      (node (ref "VD1") (pin "1") (pinfunction "C_1") (pintype "passive"))
    )
    (net (code "49") (name "Net-(VD2-C)") (class "Default")
      (node (ref "R29") (pin "2") (pinfunction "2_2") (pintype "passive"))
      (node (ref "VD2") (pin "1") (pinfunction "C_1") (pintype "passive"))
    )
    (net (code "50") (name "Net-(VT1-D)") (class "Default")
      (node (ref "VT1") (pin "3") (pinfunction "D_3") (pintype "passive"))
      (node (ref "XS3") (pin "3") (pinfunction "CTL_LED_3") (pintype "passive"))
    )
    (net (code "51") (name "Net-(VT2A-B1)") (class "Default")
      (node (ref "R30") (pin "2") (pinfunction "2_2") (pintype "passive"))
      (node (ref "VT2") (pin "5") (pinfunction "B1_5") (pintype "passive"))
    )
    (net (code "52") (name "Net-(VT2B-B2)") (class "Default")
      (node (ref "R35") (pin "2") (pinfunction "2_2") (pintype "passive"))
      (node (ref "VT2") (pin "2") (pinfunction "B2_2") (pintype "passive"))
    )
    (net (code "53") (name "Net-(VT3-D)") (class "Default")
      (node (ref "Q1") (pin "1") (pinfunction "1_1") (pintype "passive"))
      (node (ref "R26") (pin "1") (pinfunction "1_1") (pintype "passive"))
      (node (ref "VT3") (pin "3") (pinfunction "D_3") (pintype "passive"))
    )
    (net (code "54") (name "Net-(VT3-G)") (class "Default")
      (node (ref "R31") (pin "1") (pinfunction "1_1") (pintype "passive"))
      (node (ref "VT3") (pin "1") (pinfunction "G_1") (pintype "passive"))
    )
    (net (code "55") (name "Net-(VT4-D)") (class "Default")
      (node (ref "R28") (pin "1") (pinfunction "1_1") (pintype "passive"))
      (node (ref "VT4") (pin "3") (pinfunction "D_3") (pintype "passive"))
    )
    (net (code "56") (name "Net-(VT4-G)") (class "Default")
      (node (ref "R32") (pin "1") (pinfunction "1_1") (pintype "passive"))
      (node (ref "VT4") (pin "1") (pinfunction "G_1") (pintype "passive"))
    )
    (net (code "57") (name "Net-(VT5-D)") (class "Default")
      (node (ref "R29") (pin "1") (pinfunction "1_1") (pintype "passive"))
      (node (ref "VT5") (pin "3") (pinfunction "D_3") (pintype "passive"))
    )
    (net (code "58") (name "Net-(VT5-G)") (class "Default")
      (node (ref "R33") (pin "1") (pinfunction "1_1") (pintype "passive"))
      (node (ref "VT5") (pin "1") (pinfunction "G_1") (pintype "passive"))
    )
    (net (code "59") (name "Net-(XS3A-V_LED)") (class "Default")
      (node (ref "C16") (pin "2") (pinfunction "2_2") (pintype "passive"))
      (node (ref "R18") (pin "2") (pinfunction "2_2") (pintype "passive"))
      (node (ref "XS3") (pin "1") (pinfunction "V_LED_1") (pintype "passive"))
    )
    (net (code "60") (name "Net-(XS3A-Vo)") (class "Default")
      (node (ref "R20") (pin "1") (pinfunction "1_1") (pintype "passive"))
      (node (ref "XS3") (pin "5") (pinfunction "Vo_5") (pintype "passive"))
    )
    (net (code "61") (name "PGND") (class "Default")
      (node (ref "C17") (pin "2") (pinfunction "2_2") (pintype "passive"))
      (node (ref "R8") (pin "2") (pinfunction "2_2") (pintype "passive"))
      (node (ref "RV2") (pin "1") (pinfunction "1_1") (pintype "passive"))
      (node (ref "RV3") (pin "1") (pinfunction "1_1") (pintype "passive"))
      (node (ref "XS1") (pin "3") (pinfunction "3_3") (pintype "passive"))
    )
    (net (code "62") (name "VBUS") (class "Default")
      (node (ref "C13") (pin "2") (pinfunction "2_2") (pintype "passive"))
      (node (ref "C3") (pin "2") (pinfunction "2_2") (pintype "passive"))
      (node (ref "DA4") (pin "6") (pinfunction "IN2_6") (pintype "passive"))
      (node (ref "DD2") (pin "7") (pinfunction "REGIN_7") (pintype "passive"))
      (node (ref "DD2") (pin "8") (pinfunction "VBUS_8") (pintype "passive"))
      (node (ref "VD3") (pin "4") (pinfunction "4_4") (pintype "passive"))
      (node (ref "XS2") (pin "1") (pinfunction "1_1") (pintype "passive"))
    )
    (net (code "63") (name "unconnected-(DA2A-CLK-Pad2)") (class "Default")
      (node (ref "DA2") (pin "2") (pinfunction "CLK_2") (pintype "passive+no_connect"))
    )
    (net (code "64") (name "unconnected-(DA2A-IOUT1-Pad4)") (class "Default")
      (node (ref "DA2") (pin "4") (pinfunction "IOUT1_4") (pintype "passive+no_connect"))
    )
    (net (code "65") (name "unconnected-(DA4-STAT-Pad1)") (class "Default")
      (node (ref "DA4") (pin "1") (pinfunction "STAT_1") (pintype "passive+no_connect"))
    )
    (net (code "66") (name "unconnected-(DD1A-ADC{slash}TOUT-Pad2)") (class "Default")
      (node (ref "DD1") (pin "2") (pinfunction "ADC/TOUT_2") (pintype "passive+no_connect"))
    )
    (net (code "67") (name "unconnected-(DD1A-INT-Pad13)") (class "Default")
      (node (ref "DD1") (pin "13") (pinfunction "INT_13") (pintype "passive+no_connect"))
    )
    (net (code "68") (name "unconnected-(DD1A-SPI0_MISO-Pad10)") (class "Default")
      (node (ref "DD1") (pin "10") (pinfunction "SPI0_MISO_10") (pintype "passive+no_connect"))
    )
    (net (code "69") (name "unconnected-(DD1A-SPI0_MOSI-Pad9)") (class "Default")
      (node (ref "DD1") (pin "9") (pinfunction "SPI0_MOSI_9") (pintype "passive+no_connect"))
    )
    (net (code "70") (name "unconnected-(DD1A-SPI0_SCK-Pad14)") (class "Default")
      (node (ref "DD1") (pin "14") (pinfunction "SPI0_SCK_14") (pintype "passive+no_connect"))
    )
    (net (code "71") (name "unconnected-(DD2A-CTS-Pad23)") (class "Default")
      (node (ref "DD2") (pin "23") (pinfunction "CTS_23") (pintype "passive"))
    )
    (net (code "72") (name "unconnected-(DD2A-DCD-Pad1)") (class "Default")
      (node (ref "DD2") (pin "1") (pinfunction "DCD_1") (pintype "passive"))
    )
    (net (code "73") (name "unconnected-(DD2A-DSR-Pad27)") (class "Default")
      (node (ref "DD2") (pin "27") (pinfunction "DSR_27") (pintype "passive"))
    )
    (net (code "74") (name "unconnected-(DD2A-RI-Pad2)") (class "Default")
      (node (ref "DD2") (pin "2") (pinfunction "RI_2") (pintype "passive"))
    )
    (net (code "75") (name "unconnected-(DD2A-SUSPEND-Pad12)") (class "Default")
      (node (ref "DD2") (pin "12") (pinfunction "SUSPEND_12") (pintype "passive"))
    )
    (net (code "76") (name "unconnected-(DD2A-~{SUSPEND}-Pad11)") (class "Default")
      (node (ref "DD2") (pin "11") (pinfunction "~{SUSPEND}_11") (pintype "passive"))
    )
    (net (code "77") (name "unconnected-(FD1-Pad0)") (class "Default")
      (node (ref "FD1") (pin "0") (pinfunction "0_0") (pintype "passive"))
    )
    (net (code "78") (name "unconnected-(FD3-Pad0)") (class "Default")
      (node (ref "FD3") (pin "0") (pinfunction "0_0") (pintype "passive"))
    )
    (net (code "79") (name "unconnected-(FD4-Pad0)") (class "Default")
      (node (ref "FD4") (pin "0") (pinfunction "0_0") (pintype "passive"))
    )
    (net (code "80") (name "unconnected-(XS2-Pad4)") (class "Default")
      (node (ref "XS2") (pin "4") (pinfunction "4_4") (pintype "passive"))
    )
  )
)
